# HV.net
KiCad netlist of a schematic drawn in Altium Designer
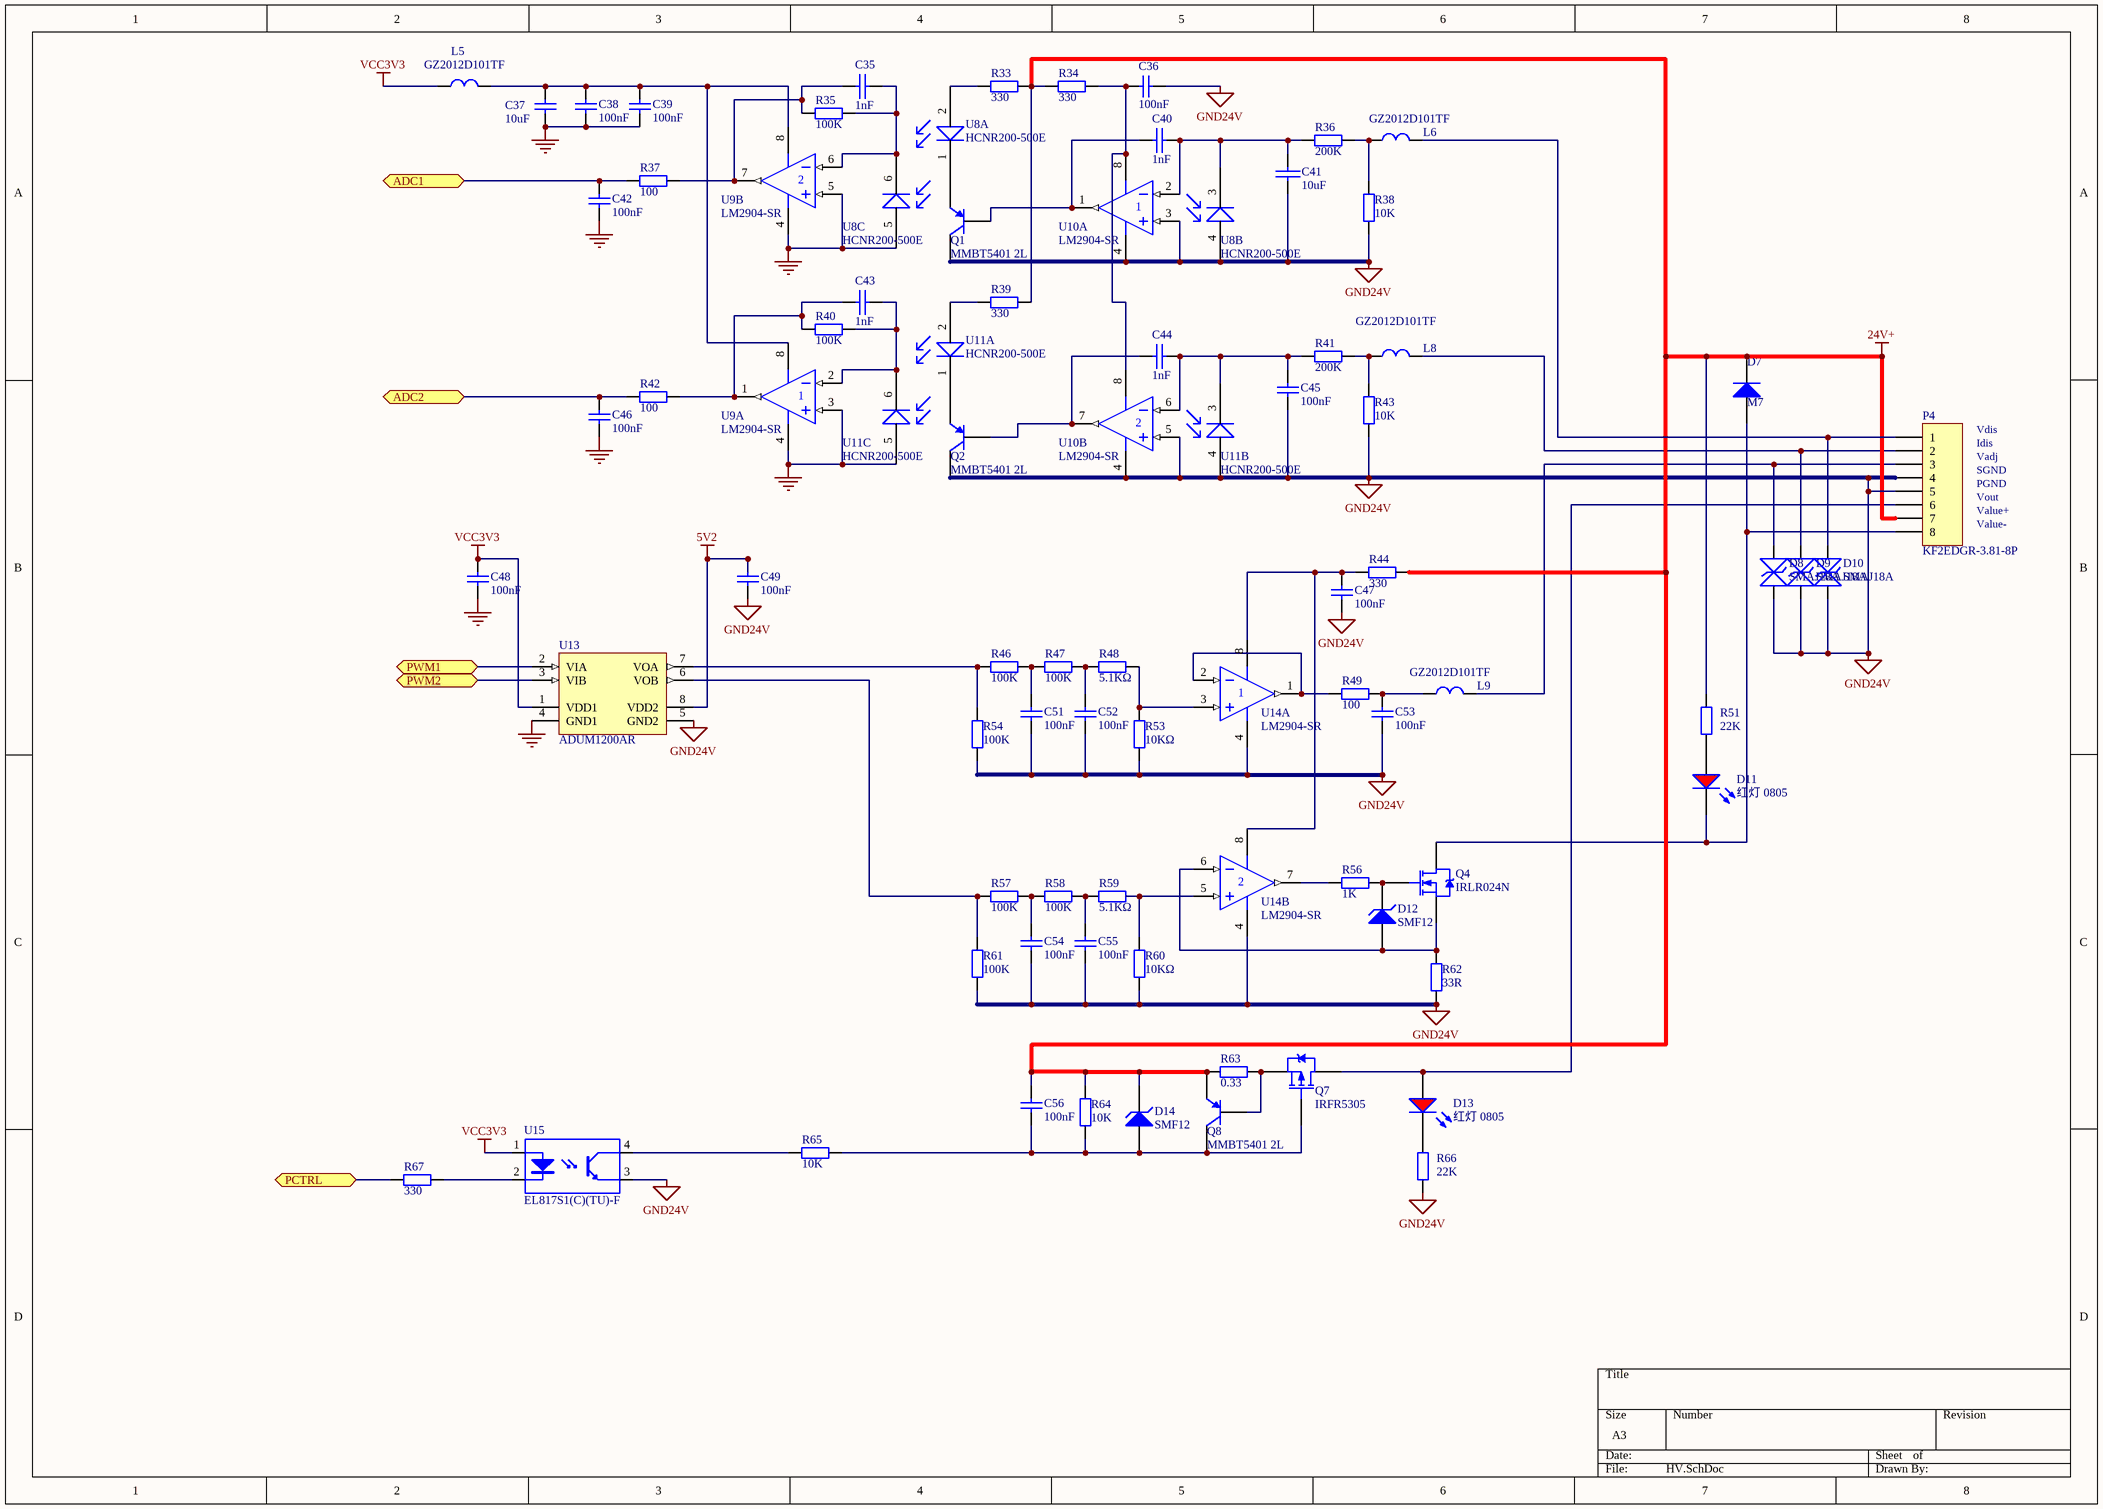
[diagram p0: HV.SchDoc]

(export (version "E")
  (design (tool "Eeschema 10.0.6"))
  (components
    (comp (ref "C35")
      (value "1nF")
      (footprint "0805_C")
      (description "Capacitor")
      (libsource (lib "*") (part "CAP"))
    )
    (comp (ref "C36")
      (value "100nF")
      (footprint "0805_C")
      (description "贴片电容")
      (libsource (lib "Miscellaneous Devices LC") (part "0805 100nF(104) 10% 50V"))
    )
    (comp (ref "C37")
      (value "10uF")
      (footprint "0805_C")
      (description "贴片电容")
      (libsource (lib "Miscellaneous Devices LC") (part "1206 10uF (106) 10% 50V"))
    )
    (comp (ref "C38")
      (value "100nF")
      (footprint "0805_C")
      (description "贴片电容")
      (libsource (lib "Miscellaneous Devices LC") (part "0805 100nF(104) 10% 50V"))
    )
    (comp (ref "C39")
      (value "100nF")
      (footprint "0805_C")
      (description "贴片电容")
      (libsource (lib "Miscellaneous Devices LC") (part "0805 100nF(104) 10% 50V"))
    )
    (comp (ref "C40")
      (value "1nF")
      (footprint "0805_C")
      (description "Capacitor")
      (libsource (lib "*") (part "CAP"))
    )
    (comp (ref "C41")
      (value "10uF")
      (footprint "0805_C")
      (description "Capacitor")
      (libsource (lib "*") (part "CC"))
    )
    (comp (ref "C42")
      (value "100nF")
      (footprint "0805_C")
      (description "贴片电容")
      (libsource (lib "Miscellaneous Devices LC") (part "0805 100nF(104) 10% 50V"))
    )
    (comp (ref "C43")
      (value "1nF")
      (footprint "0805_C")
      (description "Capacitor")
      (libsource (lib "*") (part "CAP"))
    )
    (comp (ref "C44")
      (value "1nF")
      (footprint "0805_C")
      (description "Capacitor")
      (libsource (lib "*") (part "CAP"))
    )
    (comp (ref "C45")
      (value "100nF")
      (footprint "0805_C")
      (description "贴片电容")
      (libsource (lib "Miscellaneous Devices LC") (part "0805 100nF(104) 10% 50V"))
    )
    (comp (ref "C46")
      (value "100nF")
      (footprint "0805_C")
      (description "贴片电容")
      (libsource (lib "Miscellaneous Devices LC") (part "0805 100nF(104) 10% 50V"))
    )
    (comp (ref "C47")
      (value "100nF")
      (footprint "0805_C")
      (description "贴片电容")
      (libsource (lib "Miscellaneous Devices LC") (part "0805 100nF(104) 10% 50V"))
    )
    (comp (ref "C48")
      (value "100nF")
      (footprint "0805_C")
      (description "贴片电容")
      (libsource (lib "Miscellaneous Devices LC") (part "0805 100nF(104) 10% 50V"))
    )
    (comp (ref "C49")
      (value "100nF")
      (footprint "0805_C")
      (description "贴片电容")
      (libsource (lib "Miscellaneous Devices LC") (part "0805 100nF(104) 10% 50V"))
    )
    (comp (ref "C51")
      (value "100nF")
      (footprint "0805_C")
      (description "贴片电容")
      (libsource (lib "Miscellaneous Devices LC") (part "0805 100nF(104) 10% 50V"))
    )
    (comp (ref "C52")
      (value "100nF")
      (footprint "0805_C")
      (description "贴片电容")
      (libsource (lib "Miscellaneous Devices LC") (part "0805 100nF(104) 10% 50V"))
    )
    (comp (ref "C53")
      (value "100nF")
      (footprint "0805_C")
      (description "贴片电容")
      (libsource (lib "Miscellaneous Devices LC") (part "0805 100nF(104) 10% 50V"))
    )
    (comp (ref "C54")
      (value "100nF")
      (footprint "0805_C")
      (description "贴片电容")
      (libsource (lib "Miscellaneous Devices LC") (part "0805 100nF(104) 10% 50V"))
    )
    (comp (ref "C55")
      (value "100nF")
      (footprint "0805_C")
      (description "贴片电容")
      (libsource (lib "Miscellaneous Devices LC") (part "0805 100nF(104) 10% 50V"))
    )
    (comp (ref "C56")
      (value "100nF")
      (footprint "0805_C")
      (description "贴片电容")
      (libsource (lib "Miscellaneous Devices LC") (part "0805 100nF(104) 10% 50V"))
    )
    (comp (ref "D7")
      (value "M7")
      (footprint "SMA(DO-214AC)_S1")
      (description "二极管")
      (libsource (lib "Miscellaneous Devices LC") (part "SMA(DO-214AC) M7"))
    )
    (comp (ref "D8") (value "SMAJ18A") (footprint "SMA") (libsource (lib "IC") (part "TVS")))
    (comp (ref "D9") (value "SMAJ18A") (footprint "SMA") (libsource (lib "IC") (part "TVS")))
    (comp (ref "D10") (value "SMAJ18A") (footprint "SMA") (libsource (lib "IC") (part "TVS")))
    (comp (ref "D11")
      (value "红灯 0805")
      (footprint "0805_LED_S1")
      (description "发光二极管")
      (libsource (lib "Miscellaneous Devices LC") (part "0805 红灯"))
    )
    (comp (ref "D12")
      (value "SMF12")
      (footprint "Miscellaneous Devices LC:SOD-123")
      (description "Zener Diode")
      (fields (field (name "PUBLISHER") "Altium Limited"))
      (libsource (lib "Miscellaneous Devices") (part "D Zener"))
    )
    (comp (ref "D13")
      (value "红灯 0805")
      (footprint "0805_LED_S1")
      (description "发光二极管")
      (libsource (lib "Miscellaneous Devices LC") (part "0805 红灯"))
    )
    (comp (ref "D14")
      (value "SMF12")
      (footprint "Miscellaneous Devices LC:SOD-123")
      (description "Zener Diode")
      (fields (field (name "PUBLISHER") "Altium Limited"))
      (libsource (lib "Miscellaneous Devices") (part "D Zener"))
    )
    (comp (ref "L5") (value "GZ2012D101TF") (footprint "0805_L") (libsource (lib "Devices") (part "L1")))
    (comp (ref "L6") (value "GZ2012D101TF") (footprint "0805_L") (libsource (lib "Devices") (part "L1")))
    (comp (ref "L8") (value "GZ2012D101TF") (footprint "0805_L") (libsource (lib "Devices") (part "L1")))
    (comp (ref "L9") (value "GZ2012D101TF") (footprint "0805_L") (libsource (lib "") (part "L1_1")))
    (comp (ref "P4")
      (value "KF2EDGR-3.81-8P")
      (footprint "MC1.5/8-ST-3.81")
      (description "Header, 8-Pin")
      (fields (field (name "PUBLISHER") "Altium Limited"))
      (libsource (lib "Miscellaneous Connectors") (part "Header 8"))
    )
    (comp (ref "Q1")
      (value "MMBT5401 2L")
      (footprint "SOT-23(SOT-23-3)")
      (description "三极管")
      (libsource (lib "Miscellaneous Devices LC") (part "SOT-23 MMBT5401 2L"))
    )
    (comp (ref "Q2")
      (value "MMBT5401 2L")
      (footprint "SOT-23(SOT-23-3)")
      (description "三极管")
      (libsource (lib "Miscellaneous Devices LC") (part "SOT-23 MMBT5401 2L"))
    )
    (comp (ref "Q4")
      (value "IRLR024N")
      (footprint "TO-252AA_N")
      (description "HEXFET Power MOSFET")
      (fields (field (name "PUBLISHER") "Altium Limited"))
      (libsource (lib "IR Discrete MOSFET - Power") (part "IRLR024N"))
    )
    (comp (ref "Q7")
      (value "IRFR5305")
      (footprint "TO-252AA_N")
      (description "HEXFET Power MOSFET")
      (fields (field (name "PUBLISHER") "Altium Limited"))
      (libsource (lib "IR Discrete MOSFET - Power") (part "IRFR5305"))
    )
    (comp (ref "Q8")
      (value "MMBT5401 2L")
      (footprint "SOT-23(SOT-23-3)")
      (description "三极管")
      (libsource (lib "Miscellaneous Devices LC") (part "SOT-23 MMBT5401 2L"))
    )
    (comp (ref "R33")
      (value "330")
      (footprint "0805_R")
      (description "Resistor")
      (fields (field (name "PUBLISHER") "Altium Limited"))
      (libsource (lib "") (part "Res2_3"))
    )
    (comp (ref "R34")
      (value "330")
      (footprint "0805_R")
      (description "Resistor")
      (fields (field (name "PUBLISHER") "Altium Limited"))
      (libsource (lib "") (part "Res2_3"))
    )
    (comp (ref "R35")
      (value "100K")
      (footprint "0805_R")
      (description "Resistor")
      (fields (field (name "PUBLISHER") "Altium Limited"))
      (libsource (lib "") (part "Res2_1"))
    )
    (comp (ref "R36")
      (value "200K")
      (footprint "0805_R")
      (description "Resistor")
      (fields (field (name "PUBLISHER") "Altium Limited"))
      (libsource (lib "") (part "Res2_1"))
    )
    (comp (ref "R37")
      (value "100")
      (footprint "0805_R")
      (description "Resistor")
      (fields (field (name "PUBLISHER") "Altium Limited"))
      (libsource (lib "") (part "Res2_3"))
    )
    (comp (ref "R38")
      (value "10K")
      (footprint "0805_R")
      (description "Resistor")
      (fields (field (name "PUBLISHER") "Altium Limited"))
      (libsource (lib "Miscellaneous Devices") (part "Res2"))
    )
    (comp (ref "R39")
      (value "330")
      (footprint "0805_R")
      (description "Resistor")
      (fields (field (name "PUBLISHER") "Altium Limited"))
      (libsource (lib "") (part "Res2_3"))
    )
    (comp (ref "R40")
      (value "100K")
      (footprint "0805_R")
      (description "Resistor")
      (fields (field (name "PUBLISHER") "Altium Limited"))
      (libsource (lib "") (part "Res2_1"))
    )
    (comp (ref "R41")
      (value "200K")
      (footprint "0805_R")
      (description "Resistor")
      (fields (field (name "PUBLISHER") "Altium Limited"))
      (libsource (lib "") (part "Res2_1"))
    )
    (comp (ref "R42")
      (value "100")
      (footprint "0805_R")
      (description "Resistor")
      (fields (field (name "PUBLISHER") "Altium Limited"))
      (libsource (lib "") (part "Res2_3"))
    )
    (comp (ref "R43")
      (value "10K")
      (footprint "0805_R")
      (description "Resistor")
      (fields (field (name "PUBLISHER") "Altium Limited"))
      (libsource (lib "Miscellaneous Devices") (part "Res2"))
    )
    (comp (ref "R44")
      (value "330")
      (footprint "0805_R")
      (description "贴片电阻")
      (libsource (lib "Miscellaneous Devices LC") (part "0805 100Ω (1000) 1%"))
    )
    (comp (ref "R46")
      (value "100K")
      (footprint "0805_R")
      (description "贴片电阻")
      (libsource (lib "Miscellaneous Devices LC") (part "0805 100KΩ (1003) 1%"))
    )
    (comp (ref "R47")
      (value "100K")
      (footprint "0805_R")
      (description "贴片电阻")
      (libsource (lib "Miscellaneous Devices LC") (part "0805 100KΩ (1003) 1%"))
    )
    (comp (ref "R48")
      (value "5.1KΩ")
      (footprint "0805_R")
      (description "贴片电阻")
      (libsource (lib "Miscellaneous Devices LC") (part "0805 5.1KΩ (5101) 1%"))
    )
    (comp (ref "R49")
      (value "100")
      (footprint "0805_R")
      (description "贴片电阻")
      (libsource (lib "Miscellaneous Devices LC") (part "0805 100KΩ (1003) 1%"))
    )
    (comp (ref "R51")
      (value "22K")
      (footprint "R0805")
      (description "贴片电阻")
      (libsource (lib "电阻") (part "RMK2012KBxxx（10～1M）F"))
    )
    (comp (ref "R53")
      (value "10KΩ")
      (footprint "0805_R")
      (description "贴片电阻")
      (libsource (lib "Miscellaneous Devices LC") (part "0805 10KΩ (1002) 1%"))
    )
    (comp (ref "R54")
      (value "100K")
      (footprint "0805_R")
      (description "贴片电阻")
      (libsource (lib "") (part "0805 100KΩ (1003) 1%_1"))
    )
    (comp (ref "R56")
      (value "1K")
      (footprint "0805_R")
      (description "贴片电阻")
      (libsource (lib "Miscellaneous Devices LC") (part "0805 100KΩ (1003) 1%"))
    )
    (comp (ref "R57")
      (value "100K")
      (footprint "0805_R")
      (description "贴片电阻")
      (libsource (lib "Miscellaneous Devices LC") (part "0805 100KΩ (1003) 1%"))
    )
    (comp (ref "R58")
      (value "100K")
      (footprint "0805_R")
      (description "贴片电阻")
      (libsource (lib "Miscellaneous Devices LC") (part "0805 100KΩ (1003) 1%"))
    )
    (comp (ref "R59")
      (value "5.1KΩ")
      (footprint "0805_R")
      (description "贴片电阻")
      (libsource (lib "Miscellaneous Devices LC") (part "0805 5.1KΩ (5101) 1%"))
    )
    (comp (ref "R60")
      (value "10KΩ")
      (footprint "0805_R")
      (description "贴片电阻")
      (libsource (lib "Miscellaneous Devices LC") (part "0805 10KΩ (1002) 1%"))
    )
    (comp (ref "R61")
      (value "100K")
      (footprint "0805_R")
      (description "贴片电阻")
      (libsource (lib "") (part "0805 100KΩ (1003) 1%_1"))
    )
    (comp (ref "R62")
      (value "33R")
      (footprint "R2512")
      (description "Resistor")
      (fields (field (name "PUBLISHER") "Altium Limited"))
      (libsource (lib "") (part "Res2_2"))
    )
    (comp (ref "R63")
      (value "0.33")
      (footprint "R2512")
      (description "Resistor")
      (fields (field (name "PUBLISHER") "Altium Limited"))
      (libsource (lib "") (part "Res2_5"))
    )
    (comp (ref "R64")
      (value "10K")
      (footprint "0805_R")
      (description "Resistor")
      (fields (field (name "PUBLISHER") "Altium Limited"))
      (libsource (lib "") (part "Res2_2"))
    )
    (comp (ref "R65")
      (value "10K")
      (footprint "0805_R")
      (description "Resistor")
      (fields (field (name "PUBLISHER") "Altium Limited"))
      (libsource (lib "") (part "Res2_5"))
    )
    (comp (ref "R66")
      (value "22K")
      (footprint "0805_R")
      (description "贴片电阻")
      (libsource (lib "电阻") (part "RMK2012KBxxx（10～1M）F"))
    )
    (comp (ref "R67")
      (value "330")
      (footprint "0805_R")
      (description "Resistor")
      (fields (field (name "PUBLISHER") "Altium Limited"))
      (libsource (lib "") (part "Res2_4"))
    )
    (comp (ref "U8") (value "HCNR200-500E") (footprint "SMD-8_9.0mm") (libsource (lib "*") (part "HCNR201")))
    (comp (ref "U9")
      (value "LM2904-SR")
      (footprint "SOIC-8_150mil")
      (description "Dual Low-Power Operational Amplifier")
      (fields (field (name "PUBLISHER") "Altium Limited"))
      (libsource (lib "Miscellaneous Devices LC") (part "LM2904D"))
    )
    (comp (ref "U10")
      (value "LM2904-SR")
      (footprint "SOIC-8_150mil")
      (description "Dual Low-Power Operational Amplifier")
      (fields (field (name "PUBLISHER") "Altium Limited"))
      (libsource (lib "Miscellaneous Devices LC") (part "LM2904D"))
    )
    (comp (ref "U11") (value "HCNR200-500E") (footprint "SMD-8_9.0mm") (libsource (lib "*") (part "HCNR201")))
    (comp (ref "U13")
      (value "ADUM1200AR")
      (footprint "ADI-R-8_N")
      (fields (field (name "MANUFACTURER") "Analog Devices"))
      (libsource (lib "Analog Devices Interface and Isolation Digital Isolators") (part "ADUM1200AR"))
    )
    (comp (ref "U14")
      (value "LM2904-SR")
      (footprint "SOIC-8_150mil")
      (description "Dual Low-Power Operational Amplifier")
      (fields (field (name "PUBLISHER") "Altium Limited"))
      (libsource (lib "Miscellaneous Devices LC") (part "LM2904D"))
    )
    (comp (ref "U15")
      (value "EL817S1(C)(TU)-F")
      (footprint "LC-SMD-4")
      (libsource (lib "IC") (part "TLP521"))
    )
  )
  (nets
    (net (code "1") (name "/ADC1") (class "Default")
      (node (ref "C42") (pin "2") (pinfunction "2_2") (pintype "passive"))
      (node (ref "R37") (pin "2") (pinfunction "2_2") (pintype "passive"))
    )
    (net (code "2") (name "/ADC2") (class "Default")
      (node (ref "C46") (pin "2") (pinfunction "2_2") (pintype "passive"))
      (node (ref "R42") (pin "2") (pinfunction "2_2") (pintype "passive"))
    )
    (net (code "3") (name "/PCTRL") (class "Default")
      (node (ref "R67") (pin "1") (pinfunction "1_1") (pintype "passive"))
    )
    (net (code "4") (name "/PWM1") (class "Default")
      (node (ref "U13") (pin "2") (pinfunction "VIA_2") (pintype "input"))
    )
    (net (code "5") (name "/PWM2") (class "Default")
      (node (ref "U13") (pin "3") (pinfunction "VIB_3") (pintype "input"))
    )
    (net (code "6") (name "5V2") (class "Default")
      (node (ref "C49") (pin "2") (pinfunction "2_2") (pintype "passive"))
      (node (ref "U13") (pin "8") (pinfunction "VDD2_8") (pintype "power_in"))
    )
    (net (code "7") (name "24V+") (class "Default")
      (node (ref "C56") (pin "2") (pinfunction "2_2") (pintype "passive"))
      (node (ref "D14") (pin "2") (pinfunction "K_2") (pintype "passive"))
      (node (ref "D7") (pin "2") (pinfunction "K_2") (pintype "passive"))
      (node (ref "P4") (pin "7") (pinfunction "7_7") (pintype "passive"))
      (node (ref "Q8") (pin "2") (pinfunction "E_2") (pintype "passive"))
      (node (ref "R33") (pin "1") (pinfunction "1_1") (pintype "passive"))
      (node (ref "R34") (pin "2") (pinfunction "2_2") (pintype "passive"))
      (node (ref "R39") (pin "1") (pinfunction "1_1") (pintype "passive"))
      (node (ref "R44") (pin "1") (pinfunction "1_1") (pintype "passive"))
      (node (ref "R51") (pin "1") (pinfunction "1_1") (pintype "passive"))
      (node (ref "R63") (pin "2") (pinfunction "2_2") (pintype "passive"))
      (node (ref "R64") (pin "2") (pinfunction "2_2") (pintype "passive"))
    )
    (net (code "8") (name "GND") (class "Default")
      (node (ref "C37") (pin "1") (pinfunction "1_1") (pintype "passive"))
      (node (ref "C38") (pin "1") (pinfunction "1_1") (pintype "passive"))
      (node (ref "C39") (pin "1") (pinfunction "1_1") (pintype "passive"))
      (node (ref "C42") (pin "1") (pinfunction "1_1") (pintype "passive"))
      (node (ref "C46") (pin "1") (pinfunction "1_1") (pintype "passive"))
      (node (ref "C48") (pin "1") (pinfunction "1_1") (pintype "passive"))
      (node (ref "U11") (pin "5") (pinfunction "+_5") (pintype "passive"))
      (node (ref "U13") (pin "4") (pinfunction "GND1_4") (pintype "power_in"))
      (node (ref "U8") (pin "5") (pinfunction "+_5") (pintype "passive"))
      (node (ref "U9") (pin "3") (pinfunction "IN+_3") (pintype "input"))
      (node (ref "U9") (pin "4") (pinfunction "V-_4") (pintype "power_in"))
      (node (ref "U9") (pin "5") (pinfunction "IN+_5") (pintype "input"))
    )
    (net (code "9") (name "GND24V") (class "Default")
      (node (ref "C36") (pin "1") (pinfunction "1_1") (pintype "passive"))
      (node (ref "C41") (pin "1") (pinfunction "1_1") (pintype "passive"))
      (node (ref "C45") (pin "1") (pinfunction "1_1") (pintype "passive"))
      (node (ref "C47") (pin "1") (pinfunction "1_1") (pintype "passive"))
      (node (ref "C49") (pin "1") (pinfunction "1_1") (pintype "passive"))
      (node (ref "C51") (pin "1") (pinfunction "1_1") (pintype "passive"))
      (node (ref "C52") (pin "1") (pinfunction "1_1") (pintype "passive"))
      (node (ref "C53") (pin "1") (pinfunction "1_1") (pintype "passive"))
      (node (ref "C54") (pin "1") (pinfunction "1_1") (pintype "passive"))
      (node (ref "C55") (pin "1") (pinfunction "1_1") (pintype "passive"))
      (node (ref "D10") (pin "1") (pinfunction "1_1") (pintype "passive"))
      (node (ref "D8") (pin "1") (pinfunction "1_1") (pintype "passive"))
      (node (ref "D9") (pin "1") (pinfunction "1_1") (pintype "passive"))
      (node (ref "P4") (pin "4") (pinfunction "4_4") (pintype "passive"))
      (node (ref "P4") (pin "5") (pinfunction "5_5") (pintype "passive"))
      (node (ref "Q1") (pin "3") (pinfunction "C_3") (pintype "passive"))
      (node (ref "Q2") (pin "3") (pinfunction "C_3") (pintype "passive"))
      (node (ref "R38") (pin "1") (pinfunction "1_1") (pintype "passive"))
      (node (ref "R43") (pin "1") (pinfunction "1_1") (pintype "passive"))
      (node (ref "R53") (pin "2") (pinfunction "2_2") (pintype "passive"))
      (node (ref "R54") (pin "2") (pinfunction "2_2") (pintype "passive"))
      (node (ref "R60") (pin "2") (pinfunction "2_2") (pintype "passive"))
      (node (ref "R61") (pin "2") (pinfunction "2_2") (pintype "passive"))
      (node (ref "R62") (pin "1") (pinfunction "1_1") (pintype "passive"))
      (node (ref "R66") (pin "2") (pinfunction "2_2") (pintype "passive"))
      (node (ref "U10") (pin "3") (pinfunction "IN+_3") (pintype "input"))
      (node (ref "U10") (pin "4") (pinfunction "V-_4") (pintype "power_in"))
      (node (ref "U10") (pin "5") (pinfunction "IN+_5") (pintype "input"))
      (node (ref "U11") (pin "4") (pinfunction "+_4") (pintype "passive"))
      (node (ref "U13") (pin "5") (pinfunction "GND2_5") (pintype "power_in"))
      (node (ref "U14") (pin "4") (pinfunction "V-_4") (pintype "power_in"))
      (node (ref "U15") (pin "3") (pinfunction "E_3") (pintype "passive"))
      (node (ref "U8") (pin "4") (pinfunction "+_4") (pintype "passive"))
    )
    (net (code "10") (name "Net-(C51-Pad2)") (class "Default")
      (node (ref "C51") (pin "2") (pinfunction "2_2") (pintype "passive"))
      (node (ref "R46") (pin "1") (pinfunction "1_1") (pintype "passive"))
      (node (ref "R47") (pin "2") (pinfunction "2_2") (pintype "passive"))
    )
    (net (code "11") (name "Net-(C52-Pad2)") (class "Default")
      (node (ref "C52") (pin "2") (pinfunction "2_2") (pintype "passive"))
      (node (ref "R47") (pin "1") (pinfunction "1_1") (pintype "passive"))
      (node (ref "R48") (pin "2") (pinfunction "2_2") (pintype "passive"))
    )
    (net (code "12") (name "Net-(C53-Pad2)") (class "Default")
      (node (ref "C53") (pin "2") (pinfunction "2_2") (pintype "passive"))
      (node (ref "L9") (pin "2") (pinfunction "2_2") (pintype "passive"))
      (node (ref "R49") (pin "1") (pinfunction "1_1") (pintype "passive"))
    )
    (net (code "13") (name "Net-(C54-Pad2)") (class "Default")
      (node (ref "C54") (pin "2") (pinfunction "2_2") (pintype "passive"))
      (node (ref "R57") (pin "1") (pinfunction "1_1") (pintype "passive"))
      (node (ref "R58") (pin "2") (pinfunction "2_2") (pintype "passive"))
    )
    (net (code "14") (name "Net-(C55-Pad2)") (class "Default")
      (node (ref "C55") (pin "2") (pinfunction "2_2") (pintype "passive"))
      (node (ref "R58") (pin "1") (pinfunction "1_1") (pintype "passive"))
      (node (ref "R59") (pin "2") (pinfunction "2_2") (pintype "passive"))
    )
    (net (code "15") (name "Net-(D7-A)") (class "Default")
      (node (ref "D11") (pin "K") (pinfunction "K_K") (pintype "passive"))
      (node (ref "D7") (pin "1") (pinfunction "A_1") (pintype "passive"))
      (node (ref "P4") (pin "8") (pinfunction "8_8") (pintype "passive"))
      (node (ref "Q4") (pin "4") (pinfunction "D_4") (pintype "passive"))
    )
    (net (code "16") (name "Net-(D8-Pad2)") (class "Default")
      (node (ref "D8") (pin "2") (pinfunction "2_2") (pintype "passive"))
      (node (ref "L9") (pin "1") (pinfunction "1_1") (pintype "passive"))
      (node (ref "P4") (pin "3") (pinfunction "3_3") (pintype "passive"))
    )
    (net (code "17") (name "Net-(D9-Pad2)") (class "Default")
      (node (ref "D9") (pin "2") (pinfunction "2_2") (pintype "passive"))
      (node (ref "L8") (pin "2") (pinfunction "2_2") (pintype "passive"))
      (node (ref "P4") (pin "2") (pinfunction "2_2") (pintype "passive"))
    )
    (net (code "18") (name "Net-(D10-Pad2)") (class "Default")
      (node (ref "D10") (pin "2") (pinfunction "2_2") (pintype "passive"))
      (node (ref "L6") (pin "2") (pinfunction "2_2") (pintype "passive"))
      (node (ref "P4") (pin "1") (pinfunction "1_1") (pintype "passive"))
    )
    (net (code "19") (name "Net-(D11-PadA)") (class "Default")
      (node (ref "D11") (pin "A") (pinfunction "A_A") (pintype "passive"))
      (node (ref "R51") (pin "2") (pinfunction "2_2") (pintype "passive"))
    )
    (net (code "20") (name "Net-(D12-A)") (class "Default")
      (node (ref "D12") (pin "1") (pinfunction "A_1") (pintype "passive"))
      (node (ref "Q4") (pin "3") (pinfunction "S_3") (pintype "passive"))
      (node (ref "R62") (pin "2") (pinfunction "2_2") (pintype "passive"))
      (node (ref "U14") (pin "6") (pinfunction "IN-_6") (pintype "input"))
    )
    (net (code "21") (name "Net-(D12-K)") (class "Default")
      (node (ref "D12") (pin "2") (pinfunction "K_2") (pintype "passive"))
      (node (ref "Q4") (pin "1") (pinfunction "G_1") (pintype "passive"))
      (node (ref "R56") (pin "1") (pinfunction "1_1") (pintype "passive"))
    )
    (net (code "22") (name "Net-(D13-PadK)") (class "Default")
      (node (ref "D13") (pin "K") (pinfunction "K_K") (pintype "passive"))
      (node (ref "R66") (pin "1") (pinfunction "1_1") (pintype "passive"))
    )
    (net (code "23") (name "Net-(D14-A)") (class "Default")
      (node (ref "C56") (pin "1") (pinfunction "1_1") (pintype "passive"))
      (node (ref "D14") (pin "1") (pinfunction "A_1") (pintype "passive"))
      (node (ref "Q7") (pin "1") (pinfunction "G_1") (pintype "passive"))
      (node (ref "Q8") (pin "3") (pinfunction "C_3") (pintype "passive"))
      (node (ref "R64") (pin "1") (pinfunction "1_1") (pintype "passive"))
      (node (ref "R65") (pin "1") (pinfunction "1_1") (pintype "passive"))
    )
    (net (code "24") (name "Net-(L6-Pad1)") (class "Default")
      (node (ref "L6") (pin "1") (pinfunction "1_1") (pintype "passive"))
      (node (ref "R36") (pin "2") (pinfunction "2_2") (pintype "passive"))
      (node (ref "R38") (pin "2") (pinfunction "2_2") (pintype "passive"))
    )
    (net (code "25") (name "Net-(L8-Pad1)") (class "Default")
      (node (ref "L8") (pin "1") (pinfunction "1_1") (pintype "passive"))
      (node (ref "R41") (pin "2") (pinfunction "2_2") (pintype "passive"))
      (node (ref "R43") (pin "2") (pinfunction "2_2") (pintype "passive"))
    )
    (net (code "26") (name "Net-(Q1-B)") (class "Default")
      (node (ref "C40") (pin "2") (pinfunction "2_2") (pintype "passive"))
      (node (ref "Q1") (pin "1") (pinfunction "B_1") (pintype "passive"))
      (node (ref "U10") (pin "1") (pinfunction "OUT_1") (pintype "output"))
    )
    (net (code "27") (name "Net-(Q1-E)") (class "Default")
      (node (ref "Q1") (pin "2") (pinfunction "E_2") (pintype "passive"))
      (node (ref "U8") (pin "1") (pinfunction "-_1") (pintype "passive"))
    )
    (net (code "28") (name "Net-(Q2-B)") (class "Default")
      (node (ref "C44") (pin "2") (pinfunction "2_2") (pintype "passive"))
      (node (ref "Q2") (pin "1") (pinfunction "B_1") (pintype "passive"))
      (node (ref "U10") (pin "7") (pinfunction "OUT_7") (pintype "output"))
    )
    (net (code "29") (name "Net-(Q2-E)") (class "Default")
      (node (ref "Q2") (pin "2") (pinfunction "E_2") (pintype "passive"))
      (node (ref "U11") (pin "1") (pinfunction "-_1") (pintype "passive"))
    )
    (net (code "30") (name "Net-(Q7-D)") (class "Default")
      (node (ref "D13") (pin "A") (pinfunction "A_A") (pintype "passive"))
      (node (ref "P4") (pin "6") (pinfunction "6_6") (pintype "passive"))
      (node (ref "Q7") (pin "4") (pinfunction "D_4") (pintype "passive"))
    )
    (net (code "31") (name "Net-(Q7-S)") (class "Default")
      (node (ref "Q7") (pin "3") (pinfunction "S_3") (pintype "passive"))
      (node (ref "Q8") (pin "1") (pinfunction "B_1") (pintype "passive"))
      (node (ref "R63") (pin "1") (pinfunction "1_1") (pintype "passive"))
    )
    (net (code "32") (name "Net-(U8A-+)") (class "Default")
      (node (ref "R33") (pin "2") (pinfunction "2_2") (pintype "passive"))
      (node (ref "U8") (pin "2") (pinfunction "+_2") (pintype "passive"))
    )
    (net (code "33") (name "Net-(U8C--)") (class "Default")
      (node (ref "C35") (pin "1") (pinfunction "1_1") (pintype "passive"))
      (node (ref "R35") (pin "2") (pinfunction "2_2") (pintype "passive"))
      (node (ref "U8") (pin "6") (pinfunction "-_6") (pintype "passive"))
      (node (ref "U9") (pin "6") (pinfunction "IN-_6") (pintype "input"))
    )
    (net (code "34") (name "Net-(U9A-OUT)") (class "Default")
      (node (ref "C43") (pin "2") (pinfunction "2_2") (pintype "passive"))
      (node (ref "R40") (pin "1") (pinfunction "1_1") (pintype "passive"))
      (node (ref "R42") (pin "1") (pinfunction "1_1") (pintype "passive"))
      (node (ref "U9") (pin "1") (pinfunction "OUT_1") (pintype "output"))
    )
    (net (code "35") (name "Net-(U9A-V+)") (class "Default")
      (node (ref "C37") (pin "2") (pinfunction "2_2") (pintype "passive"))
      (node (ref "C38") (pin "2") (pinfunction "2_2") (pintype "passive"))
      (node (ref "C39") (pin "2") (pinfunction "2_2") (pintype "passive"))
      (node (ref "L5") (pin "2") (pinfunction "2_2") (pintype "passive"))
      (node (ref "U9") (pin "8") (pinfunction "V+_8") (pintype "power_in"))
    )
    (net (code "36") (name "Net-(U9B-OUT)") (class "Default")
      (node (ref "C35") (pin "2") (pinfunction "2_2") (pintype "passive"))
      (node (ref "R35") (pin "1") (pinfunction "1_1") (pintype "passive"))
      (node (ref "R37") (pin "1") (pinfunction "1_1") (pintype "passive"))
      (node (ref "U9") (pin "7") (pinfunction "OUT_7") (pintype "output"))
    )
    (net (code "37") (name "Net-(U10A-IN-)") (class "Default")
      (node (ref "C40") (pin "1") (pinfunction "1_1") (pintype "passive"))
      (node (ref "C41") (pin "2") (pinfunction "2_2") (pintype "passive"))
      (node (ref "R36") (pin "1") (pinfunction "1_1") (pintype "passive"))
      (node (ref "U10") (pin "2") (pinfunction "IN-_2") (pintype "input"))
      (node (ref "U8") (pin "3") (pinfunction "-_3") (pintype "passive"))
    )
    (net (code "38") (name "Net-(U10A-V+)") (class "Default")
      (node (ref "C36") (pin "2") (pinfunction "2_2") (pintype "passive"))
      (node (ref "R34") (pin "1") (pinfunction "1_1") (pintype "passive"))
      (node (ref "U10") (pin "8") (pinfunction "V+_8") (pintype "power_in"))
    )
    (net (code "39") (name "Net-(U10B-IN-)") (class "Default")
      (node (ref "C44") (pin "1") (pinfunction "1_1") (pintype "passive"))
      (node (ref "C45") (pin "2") (pinfunction "2_2") (pintype "passive"))
      (node (ref "R41") (pin "1") (pinfunction "1_1") (pintype "passive"))
      (node (ref "U10") (pin "6") (pinfunction "IN-_6") (pintype "input"))
      (node (ref "U11") (pin "3") (pinfunction "-_3") (pintype "passive"))
    )
    (net (code "40") (name "Net-(U11A-+)") (class "Default")
      (node (ref "R39") (pin "2") (pinfunction "2_2") (pintype "passive"))
      (node (ref "U11") (pin "2") (pinfunction "+_2") (pintype "passive"))
    )
    (net (code "41") (name "Net-(U11C--)") (class "Default")
      (node (ref "C43") (pin "1") (pinfunction "1_1") (pintype "passive"))
      (node (ref "R40") (pin "2") (pinfunction "2_2") (pintype "passive"))
      (node (ref "U11") (pin "6") (pinfunction "-_6") (pintype "passive"))
      (node (ref "U9") (pin "2") (pinfunction "IN-_2") (pintype "input"))
    )
    (net (code "42") (name "Net-(U13-VOA)") (class "Default")
      (node (ref "R46") (pin "2") (pinfunction "2_2") (pintype "passive"))
      (node (ref "R54") (pin "1") (pinfunction "1_1") (pintype "passive"))
      (node (ref "U13") (pin "7") (pinfunction "VOA_7") (pintype "output"))
    )
    (net (code "43") (name "Net-(U13-VOB)") (class "Default")
      (node (ref "R57") (pin "2") (pinfunction "2_2") (pintype "passive"))
      (node (ref "R61") (pin "1") (pinfunction "1_1") (pintype "passive"))
      (node (ref "U13") (pin "6") (pinfunction "VOB_6") (pintype "output"))
    )
    (net (code "44") (name "Net-(U14A-IN+)") (class "Default")
      (node (ref "R48") (pin "1") (pinfunction "1_1") (pintype "passive"))
      (node (ref "R53") (pin "1") (pinfunction "1_1") (pintype "passive"))
      (node (ref "U14") (pin "3") (pinfunction "IN+_3") (pintype "input"))
    )
    (net (code "45") (name "Net-(U14A-IN-)") (class "Default")
      (node (ref "R49") (pin "2") (pinfunction "2_2") (pintype "passive"))
      (node (ref "U14") (pin "1") (pinfunction "OUT_1") (pintype "output"))
      (node (ref "U14") (pin "2") (pinfunction "IN-_2") (pintype "input"))
    )
    (net (code "46") (name "Net-(U14A-V+)") (class "Default")
      (node (ref "C47") (pin "2") (pinfunction "2_2") (pintype "passive"))
      (node (ref "R44") (pin "2") (pinfunction "2_2") (pintype "passive"))
      (node (ref "U14") (pin "8") (pinfunction "V+_8") (pintype "power_in"))
    )
    (net (code "47") (name "Net-(U14B-IN+)") (class "Default")
      (node (ref "R59") (pin "1") (pinfunction "1_1") (pintype "passive"))
      (node (ref "R60") (pin "1") (pinfunction "1_1") (pintype "passive"))
      (node (ref "U14") (pin "5") (pinfunction "IN+_5") (pintype "input"))
    )
    (net (code "48") (name "Net-(U14B-OUT)") (class "Default")
      (node (ref "R56") (pin "2") (pinfunction "2_2") (pintype "passive"))
      (node (ref "U14") (pin "7") (pinfunction "OUT_7") (pintype "output"))
    )
    (net (code "49") (name "Net-(U15-C)") (class "Default")
      (node (ref "R65") (pin "2") (pinfunction "2_2") (pintype "passive"))
      (node (ref "U15") (pin "4") (pinfunction "C_4") (pintype "passive"))
    )
    (net (code "50") (name "Net-(U15-K)") (class "Default")
      (node (ref "R67") (pin "2") (pinfunction "2_2") (pintype "passive"))
      (node (ref "U15") (pin "2") (pinfunction "K_2") (pintype "passive"))
    )
    (net (code "51") (name "VCC3V3") (class "Default")
      (node (ref "C48") (pin "2") (pinfunction "2_2") (pintype "passive"))
      (node (ref "L5") (pin "1") (pinfunction "1_1") (pintype "passive"))
      (node (ref "U13") (pin "1") (pinfunction "VDD1_1") (pintype "power_in"))
      (node (ref "U15") (pin "1") (pinfunction "A_1") (pintype "passive"))
    )
  )
)
